# ADC_DSP_DIFF.net
KiCad netlist of a schematic drawn in EAGLE
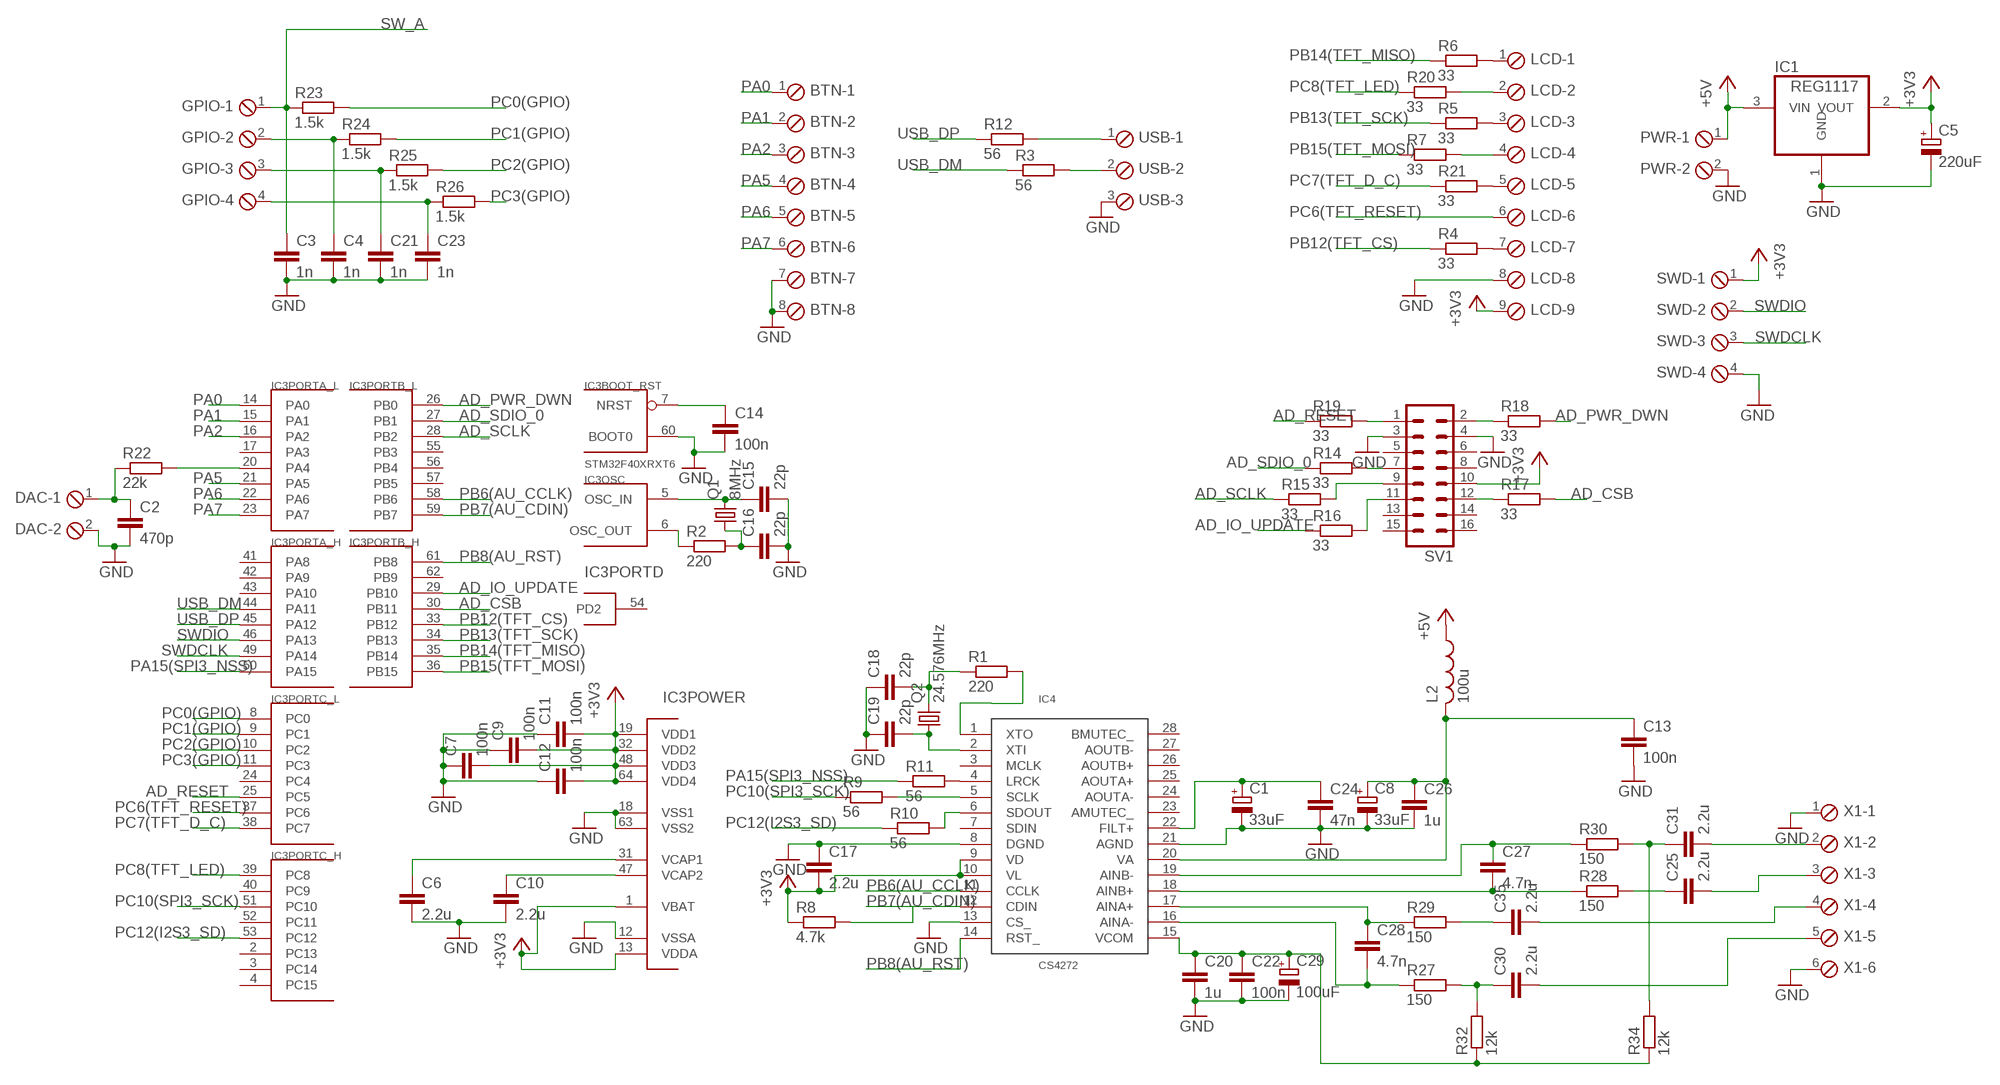
[diagram p0: schematic, sheet 1]

(export (version "E")
  (design (tool "Eeschema 10.0.6"))
  (components
    (comp (ref "BTN")
      (value "MPT8")
      (footprint "eagle-import:8POL254")
      (libsource (lib "eagle-import") (part "MPT8"))
    )
    (comp (ref "C1")
      (value "33uF")
      (footprint "eagle-import:153CLV-0605")
      (libsource (lib "eagle-import") (part "CPOL-EU153CLV-0605"))
    )
    (comp (ref "C2")
      (value "470p")
      (footprint "eagle-import:C0805")
      (libsource (lib "eagle-import") (part "C-EUC0805"))
    )
    (comp (ref "C3")
      (value "1n")
      (footprint "eagle-import:C0805")
      (libsource (lib "eagle-import") (part "C-EUC0805"))
    )
    (comp (ref "C4")
      (value "1n")
      (footprint "eagle-import:C0805")
      (libsource (lib "eagle-import") (part "C-EUC0805"))
    )
    (comp (ref "C5")
      (value "220uF")
      (footprint "eagle-import:153CLV-0605")
      (libsource (lib "eagle-import") (part "CPOL-EU153CLV-0605"))
    )
    (comp (ref "C6")
      (value "2.2u")
      (footprint "eagle-import:C0603")
      (libsource (lib "eagle-import") (part "C-EUC0603"))
    )
    (comp (ref "C7")
      (value "100n")
      (footprint "eagle-import:C0603")
      (libsource (lib "eagle-import") (part "C-EUC0603"))
    )
    (comp (ref "C8")
      (value "33uF")
      (footprint "eagle-import:153CLV-0605")
      (libsource (lib "eagle-import") (part "CPOL-EU153CLV-0605"))
    )
    (comp (ref "C9")
      (value "100n")
      (footprint "eagle-import:C0603")
      (libsource (lib "eagle-import") (part "C-EUC0603"))
    )
    (comp (ref "C10")
      (value "2.2u")
      (footprint "eagle-import:C0603")
      (libsource (lib "eagle-import") (part "C-EUC0603"))
    )
    (comp (ref "C11")
      (value "100n")
      (footprint "eagle-import:C0603")
      (libsource (lib "eagle-import") (part "C-EUC0603"))
    )
    (comp (ref "C12")
      (value "100n")
      (footprint "eagle-import:C0603")
      (libsource (lib "eagle-import") (part "C-EUC0603"))
    )
    (comp (ref "C13")
      (value "100n")
      (footprint "eagle-import:C0603")
      (libsource (lib "eagle-import") (part "C-EUC0603"))
    )
    (comp (ref "C14")
      (value "100n")
      (footprint "eagle-import:C0603")
      (libsource (lib "eagle-import") (part "C-EUC0603"))
    )
    (comp (ref "C15")
      (value "22p")
      (footprint "eagle-import:C0603")
      (libsource (lib "eagle-import") (part "C-EUC0603"))
    )
    (comp (ref "C16")
      (value "22p")
      (footprint "eagle-import:C0603")
      (libsource (lib "eagle-import") (part "C-EUC0603"))
    )
    (comp (ref "C17")
      (value "2.2u")
      (footprint "eagle-import:C0603")
      (libsource (lib "eagle-import") (part "C-EUC0603"))
    )
    (comp (ref "C18")
      (value "22p")
      (footprint "eagle-import:C0603")
      (libsource (lib "eagle-import") (part "C-EUC0603"))
    )
    (comp (ref "C19")
      (value "22p")
      (footprint "eagle-import:C0603")
      (libsource (lib "eagle-import") (part "C-EUC0603"))
    )
    (comp (ref "C20")
      (value "1u")
      (footprint "eagle-import:C0603")
      (libsource (lib "eagle-import") (part "C-EUC0603"))
    )
    (comp (ref "C21")
      (value "1n")
      (footprint "eagle-import:C0805")
      (libsource (lib "eagle-import") (part "C-EUC0805"))
    )
    (comp (ref "C22")
      (value "100n")
      (footprint "eagle-import:C0603")
      (libsource (lib "eagle-import") (part "C-EUC0603"))
    )
    (comp (ref "C23")
      (value "1n")
      (footprint "eagle-import:C0805")
      (libsource (lib "eagle-import") (part "C-EUC0805"))
    )
    (comp (ref "C24")
      (value "47n")
      (footprint "eagle-import:C0805")
      (libsource (lib "eagle-import") (part "C-EUC0805"))
    )
    (comp (ref "C25")
      (value "2.2u")
      (footprint "eagle-import:C0805")
      (libsource (lib "eagle-import") (part "C-EUC0805"))
    )
    (comp (ref "C26")
      (value "1u")
      (footprint "eagle-import:C0603")
      (libsource (lib "eagle-import") (part "C-EUC0603"))
    )
    (comp (ref "C27")
      (value "4.7n")
      (footprint "eagle-import:C0805")
      (libsource (lib "eagle-import") (part "C-EUC0805"))
    )
    (comp (ref "C28")
      (value "4.7n")
      (footprint "eagle-import:C0805")
      (libsource (lib "eagle-import") (part "C-EUC0805"))
    )
    (comp (ref "C29")
      (value "100uF")
      (footprint "eagle-import:153CLV-0605")
      (libsource (lib "eagle-import") (part "CPOL-EU153CLV-0605"))
    )
    (comp (ref "C30")
      (value "2.2u")
      (footprint "eagle-import:C0805")
      (libsource (lib "eagle-import") (part "C-EUC0805"))
    )
    (comp (ref "C31")
      (value "2.2u")
      (footprint "eagle-import:C0805")
      (libsource (lib "eagle-import") (part "C-EUC0805"))
    )
    (comp (ref "C35")
      (value "2.2u")
      (footprint "eagle-import:C0805")
      (libsource (lib "eagle-import") (part "C-EUC0805"))
    )
    (comp (ref "DAC")
      (value "MPT2")
      (footprint "eagle-import:2POL254")
      (libsource (lib "eagle-import") (part "MPT2"))
    )
    (comp (ref "GPIO")
      (value "MPT4")
      (footprint "eagle-import:4POL254")
      (libsource (lib "eagle-import") (part "MPT4"))
    )
    (comp (ref "IC1")
      (value "REG1117")
      (footprint "eagle-import:SOT223")
      (libsource (lib "eagle-import") (part "REG1117"))
    )
    (comp (ref "IC3")
      (value "STM32F40XRXT6")
      (footprint "eagle-import:TQFP64")
      (libsource (lib "eagle-import") (part "STM32F40XRXT6"))
    )
    (comp (ref "IC4")
      (value "CS4272")
      (footprint "eagle-import:TSSOP28")
      (libsource (lib "eagle-import") (part "CS4272"))
    )
    (comp (ref "L2")
      (value "100u")
      (footprint "eagle-import:0207_12")
      (libsource (lib "eagle-import") (part "L-US0207/12"))
    )
    (comp (ref "LCD")
      (value "MPT9")
      (footprint "eagle-import:9POL254")
      (libsource (lib "eagle-import") (part "MPT9"))
    )
    (comp (ref "PWR")
      (value "MPT2")
      (footprint "eagle-import:2POL254")
      (libsource (lib "eagle-import") (part "MPT2"))
    )
    (comp (ref "Q1")
      (value "8MHz")
      (footprint "eagle-import:HC49_S")
      (libsource (lib "eagle-import") (part "CRYSTALHC49S"))
    )
    (comp (ref "Q2")
      (value "24.576MHz")
      (footprint "eagle-import:HC49_S")
      (libsource (lib "eagle-import") (part "CRYSTALHC49S"))
    )
    (comp (ref "R1")
      (value "220")
      (footprint "eagle-import:R0603")
      (libsource (lib "eagle-import") (part "R-EU_R0603"))
    )
    (comp (ref "R2")
      (value "220")
      (footprint "eagle-import:R0603")
      (libsource (lib "eagle-import") (part "R-EU_R0603"))
    )
    (comp (ref "R3")
      (value "56")
      (footprint "eagle-import:R0603")
      (libsource (lib "eagle-import") (part "R-EU_R0603"))
    )
    (comp (ref "R4")
      (value "33")
      (footprint "eagle-import:R0603")
      (libsource (lib "eagle-import") (part "R-EU_R0603"))
    )
    (comp (ref "R5")
      (value "33")
      (footprint "eagle-import:R0603")
      (libsource (lib "eagle-import") (part "R-EU_R0603"))
    )
    (comp (ref "R6")
      (value "33")
      (footprint "eagle-import:R0603")
      (libsource (lib "eagle-import") (part "R-EU_R0603"))
    )
    (comp (ref "R7")
      (value "33")
      (footprint "eagle-import:R0603")
      (libsource (lib "eagle-import") (part "R-EU_R0603"))
    )
    (comp (ref "R8")
      (value "4.7k")
      (footprint "eagle-import:R0603")
      (libsource (lib "eagle-import") (part "R-EU_R0603"))
    )
    (comp (ref "R9")
      (value "56")
      (footprint "eagle-import:R0603")
      (libsource (lib "eagle-import") (part "R-EU_R0603"))
    )
    (comp (ref "R10")
      (value "56")
      (footprint "eagle-import:R0603")
      (libsource (lib "eagle-import") (part "R-EU_R0603"))
    )
    (comp (ref "R11")
      (value "56")
      (footprint "eagle-import:R0603")
      (libsource (lib "eagle-import") (part "R-EU_R0603"))
    )
    (comp (ref "R12")
      (value "56")
      (footprint "eagle-import:R0603")
      (libsource (lib "eagle-import") (part "R-EU_R0603"))
    )
    (comp (ref "R14")
      (value "33")
      (footprint "eagle-import:R0603")
      (libsource (lib "eagle-import") (part "R-EU_R0603"))
    )
    (comp (ref "R15")
      (value "33")
      (footprint "eagle-import:R0603")
      (libsource (lib "eagle-import") (part "R-EU_R0603"))
    )
    (comp (ref "R16")
      (value "33")
      (footprint "eagle-import:R0603")
      (libsource (lib "eagle-import") (part "R-EU_R0603"))
    )
    (comp (ref "R17")
      (value "33")
      (footprint "eagle-import:R0603")
      (libsource (lib "eagle-import") (part "R-EU_R0603"))
    )
    (comp (ref "R18")
      (value "33")
      (footprint "eagle-import:R0603")
      (libsource (lib "eagle-import") (part "R-EU_R0603"))
    )
    (comp (ref "R19")
      (value "33")
      (footprint "eagle-import:R0603")
      (libsource (lib "eagle-import") (part "R-EU_R0603"))
    )
    (comp (ref "R20")
      (value "33")
      (footprint "eagle-import:R0603")
      (libsource (lib "eagle-import") (part "R-EU_R0603"))
    )
    (comp (ref "R21")
      (value "33")
      (footprint "eagle-import:R0603")
      (libsource (lib "eagle-import") (part "R-EU_R0603"))
    )
    (comp (ref "R22")
      (value "22k")
      (footprint "eagle-import:R0603")
      (libsource (lib "eagle-import") (part "R-EU_R0603"))
    )
    (comp (ref "R23")
      (value "1.5k")
      (footprint "eagle-import:R0603")
      (libsource (lib "eagle-import") (part "R-EU_R0603"))
    )
    (comp (ref "R24")
      (value "1.5k")
      (footprint "eagle-import:R0603")
      (libsource (lib "eagle-import") (part "R-EU_R0603"))
    )
    (comp (ref "R25")
      (value "1.5k")
      (footprint "eagle-import:R0603")
      (libsource (lib "eagle-import") (part "R-EU_R0603"))
    )
    (comp (ref "R26")
      (value "1.5k")
      (footprint "eagle-import:R0603")
      (libsource (lib "eagle-import") (part "R-EU_R0603"))
    )
    (comp (ref "R27")
      (value "150")
      (footprint "eagle-import:R0603")
      (libsource (lib "eagle-import") (part "R-EU_R0603"))
    )
    (comp (ref "R28")
      (value "150")
      (footprint "eagle-import:R0603")
      (libsource (lib "eagle-import") (part "R-EU_R0603"))
    )
    (comp (ref "R29")
      (value "150")
      (footprint "eagle-import:R0603")
      (libsource (lib "eagle-import") (part "R-EU_R0603"))
    )
    (comp (ref "R30")
      (value "150")
      (footprint "eagle-import:R0603")
      (libsource (lib "eagle-import") (part "R-EU_R0603"))
    )
    (comp (ref "R32")
      (value "12k")
      (footprint "eagle-import:R0603")
      (libsource (lib "eagle-import") (part "R-EU_R0603"))
    )
    (comp (ref "R34")
      (value "12k")
      (footprint "eagle-import:R0603")
      (libsource (lib "eagle-import") (part "R-EU_R0603"))
    )
    (comp (ref "SV1")
      (value "ML16")
      (footprint "eagle-import:ML16")
      (libsource (lib "eagle-import") (part "ML16"))
    )
    (comp (ref "SWD")
      (value "MPT4")
      (footprint "eagle-import:4POL254")
      (libsource (lib "eagle-import") (part "MPT4"))
    )
    (comp (ref "USB")
      (value "MPT3")
      (footprint "eagle-import:3POL254")
      (libsource (lib "eagle-import") (part "MPT3"))
    )
    (comp (ref "X1")
      (value "MPT6")
      (footprint "eagle-import:6POL254")
      (libsource (lib "eagle-import") (part "MPT6"))
    )
  )
  (nets
    (net (code "1") (name "+3V3") (class "Default")
      (node (ref "C11") (pin "2") (pinfunction "2_2") (pintype "passive"))
      (node (ref "C12") (pin "2") (pinfunction "2_2") (pintype "passive"))
      (node (ref "C17") (pin "2") (pinfunction "2_2") (pintype "passive"))
      (node (ref "C5") (pin "+") (pinfunction "+_+") (pintype "passive"))
      (node (ref "C7") (pin "2") (pinfunction "2_2") (pintype "passive"))
      (node (ref "C9") (pin "2") (pinfunction "2_2") (pintype "passive"))
      (node (ref "IC1") (pin "2") (pinfunction "VOUT_2") (pintype "output"))
      (node (ref "IC3") (pin "1") (pinfunction "VBAT_1") (pintype "bidirectional"))
      (node (ref "IC3") (pin "13") (pinfunction "VDDA_13") (pintype "bidirectional"))
      (node (ref "IC3") (pin "19") (pinfunction "VDD1_19") (pintype "bidirectional"))
      (node (ref "IC3") (pin "32") (pinfunction "VDD2_32") (pintype "bidirectional"))
      (node (ref "IC3") (pin "48") (pinfunction "VDD3_48") (pintype "bidirectional"))
      (node (ref "IC3") (pin "64") (pinfunction "VDD4_64") (pintype "bidirectional"))
      (node (ref "IC4") (pin "10") (pinfunction "VL_10") (pintype "bidirectional"))
      (node (ref "IC4") (pin "9") (pinfunction "VD_9") (pintype "bidirectional"))
      (node (ref "LCD") (pin "9") (pinfunction "1_9") (pintype "passive"))
      (node (ref "R8") (pin "1") (pinfunction "1_1") (pintype "passive"))
      (node (ref "SV1") (pin "10") (pinfunction "10_10") (pintype "passive"))
      (node (ref "SWD") (pin "1") (pinfunction "1_1") (pintype "passive"))
    )
    (net (code "2") (name "+5V") (class "Default")
      (node (ref "IC1") (pin "3") (pinfunction "VIN_3") (pintype "input"))
      (node (ref "L2") (pin "1") (pinfunction "1_1") (pintype "passive"))
      (node (ref "PWR") (pin "1") (pinfunction "1_1") (pintype "passive"))
    )
    (net (code "3") (name "/AD_CSB") (class "Default")
      (node (ref "IC3") (pin "30") (pinfunction "PB11_30") (pintype "bidirectional"))
      (node (ref "R17") (pin "2") (pinfunction "2_2") (pintype "passive"))
    )
    (net (code "4") (name "/AD_IO_UPDATE") (class "Default")
      (node (ref "IC3") (pin "29") (pinfunction "PB10_29") (pintype "bidirectional"))
      (node (ref "R16") (pin "1") (pinfunction "1_1") (pintype "passive"))
    )
    (net (code "5") (name "/AD_PWR_DWN") (class "Default")
      (node (ref "IC3") (pin "26") (pinfunction "PB0_26") (pintype "bidirectional"))
      (node (ref "R18") (pin "2") (pinfunction "2_2") (pintype "passive"))
    )
    (net (code "6") (name "/AD_RESET") (class "Default")
      (node (ref "IC3") (pin "25") (pinfunction "PC5_25") (pintype "bidirectional"))
      (node (ref "R19") (pin "1") (pinfunction "1_1") (pintype "passive"))
    )
    (net (code "7") (name "/AD_SCLK") (class "Default")
      (node (ref "IC3") (pin "28") (pinfunction "PB2_28") (pintype "bidirectional"))
      (node (ref "R15") (pin "1") (pinfunction "1_1") (pintype "passive"))
    )
    (net (code "8") (name "/AD_SDIO_0") (class "Default")
      (node (ref "IC3") (pin "27") (pinfunction "PB1_27") (pintype "bidirectional"))
      (node (ref "R14") (pin "1") (pinfunction "1_1") (pintype "passive"))
    )
    (net (code "9") (name "/PA0") (class "Default")
      (node (ref "BTN") (pin "1") (pinfunction "1_1") (pintype "passive"))
      (node (ref "IC3") (pin "14") (pinfunction "PA0_14") (pintype "bidirectional"))
    )
    (net (code "10") (name "/PA1") (class "Default")
      (node (ref "BTN") (pin "2") (pinfunction "1_2") (pintype "passive"))
      (node (ref "IC3") (pin "15") (pinfunction "PA1_15") (pintype "bidirectional"))
    )
    (net (code "11") (name "/PA2") (class "Default")
      (node (ref "BTN") (pin "3") (pinfunction "1_3") (pintype "passive"))
      (node (ref "IC3") (pin "16") (pinfunction "PA2_16") (pintype "bidirectional"))
    )
    (net (code "12") (name "/PA5") (class "Default")
      (node (ref "BTN") (pin "4") (pinfunction "1_4") (pintype "passive"))
      (node (ref "IC3") (pin "21") (pinfunction "PA5_21") (pintype "bidirectional"))
    )
    (net (code "13") (name "/PA6") (class "Default")
      (node (ref "BTN") (pin "5") (pinfunction "1_5") (pintype "passive"))
      (node (ref "IC3") (pin "22") (pinfunction "PA6_22") (pintype "bidirectional"))
    )
    (net (code "14") (name "/PA7") (class "Default")
      (node (ref "BTN") (pin "6") (pinfunction "1_6") (pintype "passive"))
      (node (ref "IC3") (pin "23") (pinfunction "PA7_23") (pintype "bidirectional"))
    )
    (net (code "15") (name "/PA15(SPI3_NSS)") (class "Default")
      (node (ref "IC3") (pin "50") (pinfunction "PA15_50") (pintype "bidirectional"))
      (node (ref "R11") (pin "1") (pinfunction "1_1") (pintype "passive"))
    )
    (net (code "16") (name "/PB6(AU_CCLK)") (class "Default")
      (node (ref "IC3") (pin "58") (pinfunction "PB6_58") (pintype "bidirectional"))
      (node (ref "IC4") (pin "11") (pinfunction "CCLK_11") (pintype "bidirectional"))
    )
    (net (code "17") (name "/PB7(AU_CDIN)") (class "Default")
      (node (ref "IC3") (pin "59") (pinfunction "PB7_59") (pintype "bidirectional"))
      (node (ref "IC4") (pin "12") (pinfunction "CDIN_12") (pintype "bidirectional"))
      (node (ref "R8") (pin "2") (pinfunction "2_2") (pintype "passive"))
    )
    (net (code "18") (name "/PB8(AU_RST)") (class "Default")
      (node (ref "IC3") (pin "61") (pinfunction "PB8_61") (pintype "bidirectional"))
      (node (ref "IC4") (pin "14") (pinfunction "RST__14") (pintype "bidirectional"))
    )
    (net (code "19") (name "/PB12(TFT_CS)") (class "Default")
      (node (ref "IC3") (pin "33") (pinfunction "PB12_33") (pintype "bidirectional"))
      (node (ref "R4") (pin "1") (pinfunction "1_1") (pintype "passive"))
    )
    (net (code "20") (name "/PB13(TFT_SCK)") (class "Default")
      (node (ref "IC3") (pin "34") (pinfunction "PB13_34") (pintype "bidirectional"))
      (node (ref "R5") (pin "1") (pinfunction "1_1") (pintype "passive"))
    )
    (net (code "21") (name "/PB14(TFT_MISO)") (class "Default")
      (node (ref "IC3") (pin "35") (pinfunction "PB14_35") (pintype "bidirectional"))
      (node (ref "R6") (pin "1") (pinfunction "1_1") (pintype "passive"))
    )
    (net (code "22") (name "/PB15(TFT_MOSI)") (class "Default")
      (node (ref "IC3") (pin "36") (pinfunction "PB15_36") (pintype "bidirectional"))
      (node (ref "R7") (pin "1") (pinfunction "1_1") (pintype "passive"))
    )
    (net (code "23") (name "/PC0(GPIO)") (class "Default")
      (node (ref "IC3") (pin "8") (pinfunction "PC0_8") (pintype "bidirectional"))
      (node (ref "R23") (pin "2") (pinfunction "2_2") (pintype "passive"))
    )
    (net (code "24") (name "/PC1(GPIO)") (class "Default")
      (node (ref "IC3") (pin "9") (pinfunction "PC1_9") (pintype "bidirectional"))
      (node (ref "R24") (pin "2") (pinfunction "2_2") (pintype "passive"))
    )
    (net (code "25") (name "/PC2(GPIO)") (class "Default")
      (node (ref "IC3") (pin "10") (pinfunction "PC2_10") (pintype "bidirectional"))
      (node (ref "R25") (pin "2") (pinfunction "2_2") (pintype "passive"))
    )
    (net (code "26") (name "/PC3(GPIO)") (class "Default")
      (node (ref "IC3") (pin "11") (pinfunction "PC3_11") (pintype "bidirectional"))
      (node (ref "R26") (pin "2") (pinfunction "2_2") (pintype "passive"))
    )
    (net (code "27") (name "/PC6(TFT_RESET)") (class "Default")
      (node (ref "IC3") (pin "37") (pinfunction "PC6_37") (pintype "bidirectional"))
      (node (ref "LCD") (pin "6") (pinfunction "1_6") (pintype "passive"))
    )
    (net (code "28") (name "/PC7(TFT_D_C)") (class "Default")
      (node (ref "IC3") (pin "38") (pinfunction "PC7_38") (pintype "bidirectional"))
      (node (ref "R21") (pin "1") (pinfunction "1_1") (pintype "passive"))
    )
    (net (code "29") (name "/PC8(TFT_LED)") (class "Default")
      (node (ref "IC3") (pin "39") (pinfunction "PC8_39") (pintype "bidirectional"))
      (node (ref "R20") (pin "1") (pinfunction "1_1") (pintype "passive"))
    )
    (net (code "30") (name "/PC10(SPI3_SCK)") (class "Default")
      (node (ref "IC3") (pin "51") (pinfunction "PC10_51") (pintype "bidirectional"))
      (node (ref "R9") (pin "1") (pinfunction "1_1") (pintype "passive"))
    )
    (net (code "31") (name "/PC12(I2S3_SD)") (class "Default")
      (node (ref "IC3") (pin "53") (pinfunction "PC12_53") (pintype "bidirectional"))
      (node (ref "R10") (pin "1") (pinfunction "1_1") (pintype "passive"))
    )
    (net (code "32") (name "/SWDCLK") (class "Default")
      (node (ref "IC3") (pin "49") (pinfunction "PA14_49") (pintype "bidirectional"))
      (node (ref "SWD") (pin "3") (pinfunction "1_3") (pintype "passive"))
    )
    (net (code "33") (name "/SWDIO") (class "Default")
      (node (ref "IC3") (pin "46") (pinfunction "PA13_46") (pintype "bidirectional"))
      (node (ref "SWD") (pin "2") (pinfunction "1_2") (pintype "passive"))
    )
    (net (code "34") (name "/SW_A") (class "Default")
      (node (ref "C3") (pin "1") (pinfunction "1_1") (pintype "passive"))
      (node (ref "GPIO") (pin "1") (pinfunction "1_1") (pintype "passive"))
      (node (ref "R23") (pin "1") (pinfunction "1_1") (pintype "passive"))
    )
    (net (code "35") (name "/USB_DM") (class "Default")
      (node (ref "IC3") (pin "44") (pinfunction "PA11_44") (pintype "bidirectional"))
      (node (ref "R3") (pin "1") (pinfunction "1_1") (pintype "passive"))
    )
    (net (code "36") (name "/USB_DP") (class "Default")
      (node (ref "IC3") (pin "45") (pinfunction "PA12_45") (pintype "bidirectional"))
      (node (ref "R12") (pin "1") (pinfunction "1_1") (pintype "passive"))
    )
    (net (code "37") (name "GND") (class "Default")
      (node (ref "BTN") (pin "7") (pinfunction "1_7") (pintype "passive"))
      (node (ref "BTN") (pin "8") (pinfunction "1_8") (pintype "passive"))
      (node (ref "C1") (pin "-") (pinfunction "-_-") (pintype "passive"))
      (node (ref "C10") (pin "2") (pinfunction "2_2") (pintype "passive"))
      (node (ref "C11") (pin "1") (pinfunction "1_1") (pintype "passive"))
      (node (ref "C12") (pin "1") (pinfunction "1_1") (pintype "passive"))
      (node (ref "C13") (pin "2") (pinfunction "2_2") (pintype "passive"))
      (node (ref "C14") (pin "2") (pinfunction "2_2") (pintype "passive"))
      (node (ref "C15") (pin "2") (pinfunction "2_2") (pintype "passive"))
      (node (ref "C16") (pin "2") (pinfunction "2_2") (pintype "passive"))
      (node (ref "C17") (pin "1") (pinfunction "1_1") (pintype "passive"))
      (node (ref "C18") (pin "1") (pinfunction "1_1") (pintype "passive"))
      (node (ref "C19") (pin "1") (pinfunction "1_1") (pintype "passive"))
      (node (ref "C2") (pin "2") (pinfunction "2_2") (pintype "passive"))
      (node (ref "C20") (pin "2") (pinfunction "2_2") (pintype "passive"))
      (node (ref "C21") (pin "2") (pinfunction "2_2") (pintype "passive"))
      (node (ref "C22") (pin "2") (pinfunction "2_2") (pintype "passive"))
      (node (ref "C23") (pin "2") (pinfunction "2_2") (pintype "passive"))
      (node (ref "C24") (pin "2") (pinfunction "2_2") (pintype "passive"))
      (node (ref "C26") (pin "2") (pinfunction "2_2") (pintype "passive"))
      (node (ref "C29") (pin "-") (pinfunction "-_-") (pintype "passive"))
      (node (ref "C3") (pin "2") (pinfunction "2_2") (pintype "passive"))
      (node (ref "C4") (pin "2") (pinfunction "2_2") (pintype "passive"))
      (node (ref "C5") (pin "-") (pinfunction "-_-") (pintype "passive"))
      (node (ref "C6") (pin "2") (pinfunction "2_2") (pintype "passive"))
      (node (ref "C7") (pin "1") (pinfunction "1_1") (pintype "passive"))
      (node (ref "C8") (pin "-") (pinfunction "-_-") (pintype "passive"))
      (node (ref "C9") (pin "1") (pinfunction "1_1") (pintype "passive"))
      (node (ref "DAC") (pin "2") (pinfunction "1_2") (pintype "passive"))
      (node (ref "IC1") (pin "1") (pinfunction "GND_1") (pintype "power_in"))
      (node (ref "IC3") (pin "12") (pinfunction "VSSA_12") (pintype "bidirectional"))
      (node (ref "IC3") (pin "18") (pinfunction "VSS1_18") (pintype "bidirectional"))
      (node (ref "IC3") (pin "60") (pinfunction "BOOT0_60") (pintype "input"))
      (node (ref "IC3") (pin "63") (pinfunction "VSS2_63") (pintype "bidirectional"))
      (node (ref "IC4") (pin "13") (pinfunction "CS__13") (pintype "bidirectional"))
      (node (ref "IC4") (pin "21") (pinfunction "AGND_21") (pintype "bidirectional"))
      (node (ref "IC4") (pin "8") (pinfunction "DGND_8") (pintype "bidirectional"))
      (node (ref "LCD") (pin "8") (pinfunction "1_8") (pintype "passive"))
      (node (ref "PWR") (pin "2") (pinfunction "1_2") (pintype "passive"))
      (node (ref "SV1") (pin "3") (pinfunction "3_3") (pintype "passive"))
      (node (ref "SV1") (pin "4") (pinfunction "4_4") (pintype "passive"))
      (node (ref "SWD") (pin "4") (pinfunction "1_4") (pintype "passive"))
      (node (ref "USB") (pin "3") (pinfunction "1_3") (pintype "passive"))
      (node (ref "X1") (pin "1") (pinfunction "1_1") (pintype "passive"))
      (node (ref "X1") (pin "6") (pinfunction "1_6") (pintype "passive"))
    )
    (net (code "38") (name "Net-(C2-Pad1)") (class "Default")
      (node (ref "C2") (pin "1") (pinfunction "1_1") (pintype "passive"))
      (node (ref "DAC") (pin "1") (pinfunction "1_1") (pintype "passive"))
      (node (ref "R22") (pin "1") (pinfunction "1_1") (pintype "passive"))
    )
    (net (code "39") (name "Net-(C16-Pad1)") (class "Default")
      (node (ref "C16") (pin "1") (pinfunction "1_1") (pintype "passive"))
      (node (ref "Q1") (pin "1") (pinfunction "1_1") (pintype "passive"))
      (node (ref "R2") (pin "2") (pinfunction "2_2") (pintype "passive"))
    )
    (net (code "40") (name "Net-(C18-Pad2)") (class "Default")
      (node (ref "C18") (pin "2") (pinfunction "2_2") (pintype "passive"))
      (node (ref "Q2") (pin "2") (pinfunction "2_2") (pintype "passive"))
      (node (ref "R1") (pin "1") (pinfunction "1_1") (pintype "passive"))
    )
    (net (code "41") (name "Net-(C25-Pad1)") (class "Default")
      (node (ref "C25") (pin "1") (pinfunction "1_1") (pintype "passive"))
      (node (ref "R28") (pin "2") (pinfunction "2_2") (pintype "passive"))
    )
    (net (code "42") (name "Net-(C30-Pad1)") (class "Default")
      (node (ref "C30") (pin "1") (pinfunction "1_1") (pintype "passive"))
      (node (ref "R27") (pin "2") (pinfunction "2_2") (pintype "passive"))
      (node (ref "R32") (pin "2") (pinfunction "2_2") (pintype "passive"))
    )
    (net (code "43") (name "Net-(C31-Pad1)") (class "Default")
      (node (ref "C31") (pin "1") (pinfunction "1_1") (pintype "passive"))
      (node (ref "R30") (pin "2") (pinfunction "2_2") (pintype "passive"))
      (node (ref "R34") (pin "2") (pinfunction "2_2") (pintype "passive"))
    )
    (net (code "44") (name "Net-(C35-Pad1)") (class "Default")
      (node (ref "C35") (pin "1") (pinfunction "1_1") (pintype "passive"))
      (node (ref "R29") (pin "2") (pinfunction "2_2") (pintype "passive"))
    )
    (net (code "45") (name "Net-(GPIOB-1)") (class "Default")
      (node (ref "C4") (pin "1") (pinfunction "1_1") (pintype "passive"))
      (node (ref "GPIO") (pin "2") (pinfunction "1_2") (pintype "passive"))
      (node (ref "R24") (pin "1") (pinfunction "1_1") (pintype "passive"))
    )
    (net (code "46") (name "Net-(GPIOC-1)") (class "Default")
      (node (ref "C21") (pin "1") (pinfunction "1_1") (pintype "passive"))
      (node (ref "GPIO") (pin "3") (pinfunction "1_3") (pintype "passive"))
      (node (ref "R25") (pin "1") (pinfunction "1_1") (pintype "passive"))
    )
    (net (code "47") (name "Net-(GPIOD-1)") (class "Default")
      (node (ref "C23") (pin "1") (pinfunction "1_1") (pintype "passive"))
      (node (ref "GPIO") (pin "4") (pinfunction "1_4") (pintype "passive"))
      (node (ref "R26") (pin "1") (pinfunction "1_1") (pintype "passive"))
    )
    (net (code "48") (name "Net-(IC3A-NRST)") (class "Default")
      (node (ref "C14") (pin "1") (pinfunction "1_1") (pintype "passive"))
      (node (ref "IC3") (pin "7") (pinfunction "NRST_7") (pintype "input"))
    )
    (net (code "49") (name "Net-(IC3B-OSC_IN)") (class "Default")
      (node (ref "C15") (pin "1") (pinfunction "1_1") (pintype "passive"))
      (node (ref "IC3") (pin "5") (pinfunction "OSC_IN_5") (pintype "input"))
      (node (ref "Q1") (pin "2") (pinfunction "2_2") (pintype "passive"))
    )
    (net (code "50") (name "Net-(IC3B-OSC_OUT)") (class "Default")
      (node (ref "IC3") (pin "6") (pinfunction "OSC_OUT_6") (pintype "output"))
      (node (ref "R2") (pin "1") (pinfunction "1_1") (pintype "passive"))
    )
    (net (code "51") (name "Net-(IC3D-PA4)") (class "Default")
      (node (ref "IC3") (pin "20") (pinfunction "PA4_20") (pintype "bidirectional"))
      (node (ref "R22") (pin "2") (pinfunction "2_2") (pintype "passive"))
    )
    (net (code "52") (name "Net-(IC3J-VCAP1)") (class "Default")
      (node (ref "C6") (pin "1") (pinfunction "1_1") (pintype "passive"))
      (node (ref "IC3") (pin "31") (pinfunction "VCAP1_31") (pintype "bidirectional"))
    )
    (net (code "53") (name "Net-(IC3J-VCAP2)") (class "Default")
      (node (ref "C10") (pin "1") (pinfunction "1_1") (pintype "passive"))
      (node (ref "IC3") (pin "47") (pinfunction "VCAP2_47") (pintype "bidirectional"))
    )
    (net (code "54") (name "Net-(IC4-AINA+)") (class "Default")
      (node (ref "C28") (pin "1") (pinfunction "1_1") (pintype "passive"))
      (node (ref "IC4") (pin "17") (pinfunction "AINA+_17") (pintype "bidirectional"))
      (node (ref "R29") (pin "1") (pinfunction "1_1") (pintype "passive"))
    )
    (net (code "55") (name "Net-(IC4-AINA-)") (class "Default")
      (node (ref "C28") (pin "2") (pinfunction "2_2") (pintype "passive"))
      (node (ref "IC4") (pin "16") (pinfunction "AINA-_16") (pintype "bidirectional"))
      (node (ref "R27") (pin "1") (pinfunction "1_1") (pintype "passive"))
    )
    (net (code "56") (name "Net-(IC4-AINB+)") (class "Default")
      (node (ref "C27") (pin "2") (pinfunction "2_2") (pintype "passive"))
      (node (ref "IC4") (pin "18") (pinfunction "AINB+_18") (pintype "bidirectional"))
      (node (ref "R28") (pin "1") (pinfunction "1_1") (pintype "passive"))
    )
    (net (code "57") (name "Net-(IC4-AINB-)") (class "Default")
      (node (ref "C27") (pin "1") (pinfunction "1_1") (pintype "passive"))
      (node (ref "IC4") (pin "19") (pinfunction "AINB-_19") (pintype "bidirectional"))
      (node (ref "R30") (pin "1") (pinfunction "1_1") (pintype "passive"))
    )
    (net (code "58") (name "Net-(IC4-FILT+)") (class "Default")
      (node (ref "C1") (pin "+") (pinfunction "+_+") (pintype "passive"))
      (node (ref "C24") (pin "1") (pinfunction "1_1") (pintype "passive"))
      (node (ref "IC4") (pin "22") (pinfunction "FILT+_22") (pintype "bidirectional"))
    )
    (net (code "59") (name "Net-(IC4-LRCK)") (class "Default")
      (node (ref "IC4") (pin "4") (pinfunction "LRCK_4") (pintype "bidirectional"))
      (node (ref "R11") (pin "2") (pinfunction "2_2") (pintype "passive"))
    )
    (net (code "60") (name "Net-(IC4-SCLK)") (class "Default")
      (node (ref "IC4") (pin "5") (pinfunction "SCLK_5") (pintype "bidirectional"))
      (node (ref "R9") (pin "2") (pinfunction "2_2") (pintype "passive"))
    )
    (net (code "61") (name "Net-(IC4-SDOUT)") (class "Default")
      (node (ref "IC4") (pin "6") (pinfunction "SDOUT_6") (pintype "bidirectional"))
      (node (ref "R10") (pin "2") (pinfunction "2_2") (pintype "passive"))
    )
    (net (code "62") (name "Net-(IC4-VA)") (class "Default")
      (node (ref "C13") (pin "1") (pinfunction "1_1") (pintype "passive"))
      (node (ref "C26") (pin "1") (pinfunction "1_1") (pintype "passive"))
      (node (ref "C8") (pin "+") (pinfunction "+_+") (pintype "passive"))
      (node (ref "IC4") (pin "20") (pinfunction "VA_20") (pintype "bidirectional"))
      (node (ref "L2") (pin "2") (pinfunction "2_2") (pintype "passive"))
    )
    (net (code "63") (name "Net-(IC4-VCOM)") (class "Default")
      (node (ref "C20") (pin "1") (pinfunction "1_1") (pintype "passive"))
      (node (ref "C22") (pin "1") (pinfunction "1_1") (pintype "passive"))
      (node (ref "C29") (pin "+") (pinfunction "+_+") (pintype "passive"))
      (node (ref "IC4") (pin "15") (pinfunction "VCOM_15") (pintype "bidirectional"))
      (node (ref "R32") (pin "1") (pinfunction "1_1") (pintype "passive"))
      (node (ref "R34") (pin "1") (pinfunction "1_1") (pintype "passive"))
    )
    (net (code "64") (name "Net-(IC4-XTI)") (class "Default")
      (node (ref "C19") (pin "2") (pinfunction "2_2") (pintype "passive"))
      (node (ref "IC4") (pin "2") (pinfunction "XTI_2") (pintype "bidirectional"))
      (node (ref "Q2") (pin "1") (pinfunction "1_1") (pintype "passive"))
    )
    (net (code "65") (name "Net-(IC4-XTO)") (class "Default")
      (node (ref "IC4") (pin "1") (pinfunction "XTO_1") (pintype "bidirectional"))
      (node (ref "R1") (pin "2") (pinfunction "2_2") (pintype "passive"))
    )
    (net (code "66") (name "Net-(LCD-Pad1)") (class "Default")
      (node (ref "LCD") (pin "1") (pinfunction "1_1") (pintype "passive"))
      (node (ref "R6") (pin "2") (pinfunction "2_2") (pintype "passive"))
    )
    (net (code "67") (name "Net-(LCDB-1)") (class "Default")
      (node (ref "LCD") (pin "2") (pinfunction "1_2") (pintype "passive"))
      (node (ref "R20") (pin "2") (pinfunction "2_2") (pintype "passive"))
    )
    (net (code "68") (name "Net-(LCDC-1)") (class "Default")
      (node (ref "LCD") (pin "3") (pinfunction "1_3") (pintype "passive"))
      (node (ref "R5") (pin "2") (pinfunction "2_2") (pintype "passive"))
    )
    (net (code "69") (name "Net-(LCDD-1)") (class "Default")
      (node (ref "LCD") (pin "4") (pinfunction "1_4") (pintype "passive"))
      (node (ref "R7") (pin "2") (pinfunction "2_2") (pintype "passive"))
    )
    (net (code "70") (name "Net-(LCDE-1)") (class "Default")
      (node (ref "LCD") (pin "5") (pinfunction "1_5") (pintype "passive"))
      (node (ref "R21") (pin "2") (pinfunction "2_2") (pintype "passive"))
    )
    (net (code "71") (name "Net-(LCDG-1)") (class "Default")
      (node (ref "LCD") (pin "7") (pinfunction "1_7") (pintype "passive"))
      (node (ref "R4") (pin "2") (pinfunction "2_2") (pintype "passive"))
    )
    (net (code "72") (name "Net-(R12-Pad2)") (class "Default")
      (node (ref "R12") (pin "2") (pinfunction "2_2") (pintype "passive"))
      (node (ref "USB") (pin "1") (pinfunction "1_1") (pintype "passive"))
    )
    (net (code "73") (name "Net-(R14-Pad2)") (class "Default")
      (node (ref "R14") (pin "2") (pinfunction "2_2") (pintype "passive"))
      (node (ref "SV1") (pin "7") (pinfunction "7_7") (pintype "passive"))
    )
    (net (code "74") (name "Net-(R15-Pad2)") (class "Default")
      (node (ref "R15") (pin "2") (pinfunction "2_2") (pintype "passive"))
      (node (ref "SV1") (pin "9") (pinfunction "9_9") (pintype "passive"))
    )
    (net (code "75") (name "Net-(R16-Pad2)") (class "Default")
      (node (ref "R16") (pin "2") (pinfunction "2_2") (pintype "passive"))
      (node (ref "SV1") (pin "11") (pinfunction "11_11") (pintype "passive"))
    )
    (net (code "76") (name "Net-(R17-Pad1)") (class "Default")
      (node (ref "R17") (pin "1") (pinfunction "1_1") (pintype "passive"))
      (node (ref "SV1") (pin "12") (pinfunction "12_12") (pintype "passive"))
    )
    (net (code "77") (name "Net-(R18-Pad1)") (class "Default")
      (node (ref "R18") (pin "1") (pinfunction "1_1") (pintype "passive"))
      (node (ref "SV1") (pin "2") (pinfunction "2_2") (pintype "passive"))
    )
    (net (code "78") (name "Net-(R19-Pad2)") (class "Default")
      (node (ref "R19") (pin "2") (pinfunction "2_2") (pintype "passive"))
      (node (ref "SV1") (pin "1") (pinfunction "1_1") (pintype "passive"))
    )
    (net (code "79") (name "Net-(USBB-1)") (class "Default")
      (node (ref "R3") (pin "2") (pinfunction "2_2") (pintype "passive"))
      (node (ref "USB") (pin "2") (pinfunction "1_2") (pintype "passive"))
    )
    (net (code "80") (name "Net-(X1B-1)") (class "Default")
      (node (ref "C31") (pin "2") (pinfunction "2_2") (pintype "passive"))
      (node (ref "X1") (pin "2") (pinfunction "1_2") (pintype "passive"))
    )
    (net (code "81") (name "Net-(X1C-1)") (class "Default")
      (node (ref "C25") (pin "2") (pinfunction "2_2") (pintype "passive"))
      (node (ref "X1") (pin "3") (pinfunction "1_3") (pintype "passive"))
    )
    (net (code "82") (name "Net-(X1D-1)") (class "Default")
      (node (ref "C35") (pin "2") (pinfunction "2_2") (pintype "passive"))
      (node (ref "X1") (pin "4") (pinfunction "1_4") (pintype "passive"))
    )
    (net (code "83") (name "Net-(X1E-1)") (class "Default")
      (node (ref "C30") (pin "2") (pinfunction "2_2") (pintype "passive"))
      (node (ref "X1") (pin "5") (pinfunction "1_5") (pintype "passive"))
    )
    (net (code "84") (name "unconnected-(IC3C-PA8-Pad41)") (class "Default")
      (node (ref "IC3") (pin "41") (pinfunction "PA8_41") (pintype "bidirectional"))
    )
    (net (code "85") (name "unconnected-(IC3C-PA9-Pad42)") (class "Default")
      (node (ref "IC3") (pin "42") (pinfunction "PA9_42") (pintype "bidirectional"))
    )
    (net (code "86") (name "unconnected-(IC3C-PA10-Pad43)") (class "Default")
      (node (ref "IC3") (pin "43") (pinfunction "PA10_43") (pintype "bidirectional"))
    )
    (net (code "87") (name "unconnected-(IC3D-PA3-Pad17)") (class "Default")
      (node (ref "IC3") (pin "17") (pinfunction "PA3_17") (pintype "bidirectional"))
    )
    (net (code "88") (name "unconnected-(IC3E-PB9-Pad62)") (class "Default")
      (node (ref "IC3") (pin "62") (pinfunction "PB9_62") (pintype "bidirectional"))
    )
    (net (code "89") (name "unconnected-(IC3F-PB3-Pad55)") (class "Default")
      (node (ref "IC3") (pin "55") (pinfunction "PB3_55") (pintype "bidirectional"))
    )
    (net (code "90") (name "unconnected-(IC3F-PB4-Pad56)") (class "Default")
      (node (ref "IC3") (pin "56") (pinfunction "PB4_56") (pintype "bidirectional"))
    )
    (net (code "91") (name "unconnected-(IC3F-PB5-Pad57)") (class "Default")
      (node (ref "IC3") (pin "57") (pinfunction "PB5_57") (pintype "bidirectional"))
    )
    (net (code "92") (name "unconnected-(IC3G-PC9-Pad40)") (class "Default")
      (node (ref "IC3") (pin "40") (pinfunction "PC9_40") (pintype "bidirectional"))
    )
    (net (code "93") (name "unconnected-(IC3G-PC11-Pad52)") (class "Default")
      (node (ref "IC3") (pin "52") (pinfunction "PC11_52") (pintype "bidirectional"))
    )
    (net (code "94") (name "unconnected-(IC3G-PC13-Pad2)") (class "Default")
      (node (ref "IC3") (pin "2") (pinfunction "PC13_2") (pintype "bidirectional"))
    )
    (net (code "95") (name "unconnected-(IC3G-PC14-Pad3)") (class "Default")
      (node (ref "IC3") (pin "3") (pinfunction "PC14_3") (pintype "bidirectional"))
    )
    (net (code "96") (name "unconnected-(IC3G-PC15-Pad4)") (class "Default")
      (node (ref "IC3") (pin "4") (pinfunction "PC15_4") (pintype "bidirectional"))
    )
    (net (code "97") (name "unconnected-(IC3H-PC4-Pad24)") (class "Default")
      (node (ref "IC3") (pin "24") (pinfunction "PC4_24") (pintype "bidirectional"))
    )
    (net (code "98") (name "unconnected-(IC3I-PD2-Pad54)") (class "Default")
      (node (ref "IC3") (pin "54") (pinfunction "PD2_54") (pintype "bidirectional"))
    )
    (net (code "99") (name "unconnected-(IC4-AMUTEC_-Pad23)") (class "Default")
      (node (ref "IC4") (pin "23") (pinfunction "AMUTEC__23") (pintype "bidirectional"))
    )
    (net (code "100") (name "unconnected-(IC4-AOUTA+-Pad25)") (class "Default")
      (node (ref "IC4") (pin "25") (pinfunction "AOUTA+_25") (pintype "bidirectional"))
    )
    (net (code "101") (name "unconnected-(IC4-AOUTA--Pad24)") (class "Default")
      (node (ref "IC4") (pin "24") (pinfunction "AOUTA-_24") (pintype "bidirectional"))
    )
    (net (code "102") (name "unconnected-(IC4-AOUTB+-Pad26)") (class "Default")
      (node (ref "IC4") (pin "26") (pinfunction "AOUTB+_26") (pintype "bidirectional"))
    )
    (net (code "103") (name "unconnected-(IC4-AOUTB--Pad27)") (class "Default")
      (node (ref "IC4") (pin "27") (pinfunction "AOUTB-_27") (pintype "bidirectional"))
    )
    (net (code "104") (name "unconnected-(IC4-BMUTEC_-Pad28)") (class "Default")
      (node (ref "IC4") (pin "28") (pinfunction "BMUTEC__28") (pintype "bidirectional"))
    )
    (net (code "105") (name "unconnected-(IC4-MCLK-Pad3)") (class "Default")
      (node (ref "IC4") (pin "3") (pinfunction "MCLK_3") (pintype "bidirectional"))
    )
    (net (code "106") (name "unconnected-(IC4-SDIN-Pad7)") (class "Default")
      (node (ref "IC4") (pin "7") (pinfunction "SDIN_7") (pintype "bidirectional"))
    )
    (net (code "107") (name "unconnected-(SV1-Pad5)") (class "Default")
      (node (ref "SV1") (pin "5") (pinfunction "5_5") (pintype "passive"))
    )
    (net (code "108") (name "unconnected-(SV1-Pad6)") (class "Default")
      (node (ref "SV1") (pin "6") (pinfunction "6_6") (pintype "passive"))
    )
    (net (code "109") (name "unconnected-(SV1-Pad8)") (class "Default")
      (node (ref "SV1") (pin "8") (pinfunction "8_8") (pintype "passive"))
    )
    (net (code "110") (name "unconnected-(SV1-Pad13)") (class "Default")
      (node (ref "SV1") (pin "13") (pinfunction "13_13") (pintype "passive"))
    )
    (net (code "111") (name "unconnected-(SV1-Pad14)") (class "Default")
      (node (ref "SV1") (pin "14") (pinfunction "14_14") (pintype "passive"))
    )
    (net (code "112") (name "unconnected-(SV1-Pad15)") (class "Default")
      (node (ref "SV1") (pin "15") (pinfunction "15_15") (pintype "passive"))
    )
    (net (code "113") (name "unconnected-(SV1-Pad16)") (class "Default")
      (node (ref "SV1") (pin "16") (pinfunction "16_16") (pintype "passive"))
    )
  )
)
